# Sheet5_MCU_PowerDecoupling.net
KiCad netlist of a schematic drawn in Altium Designer
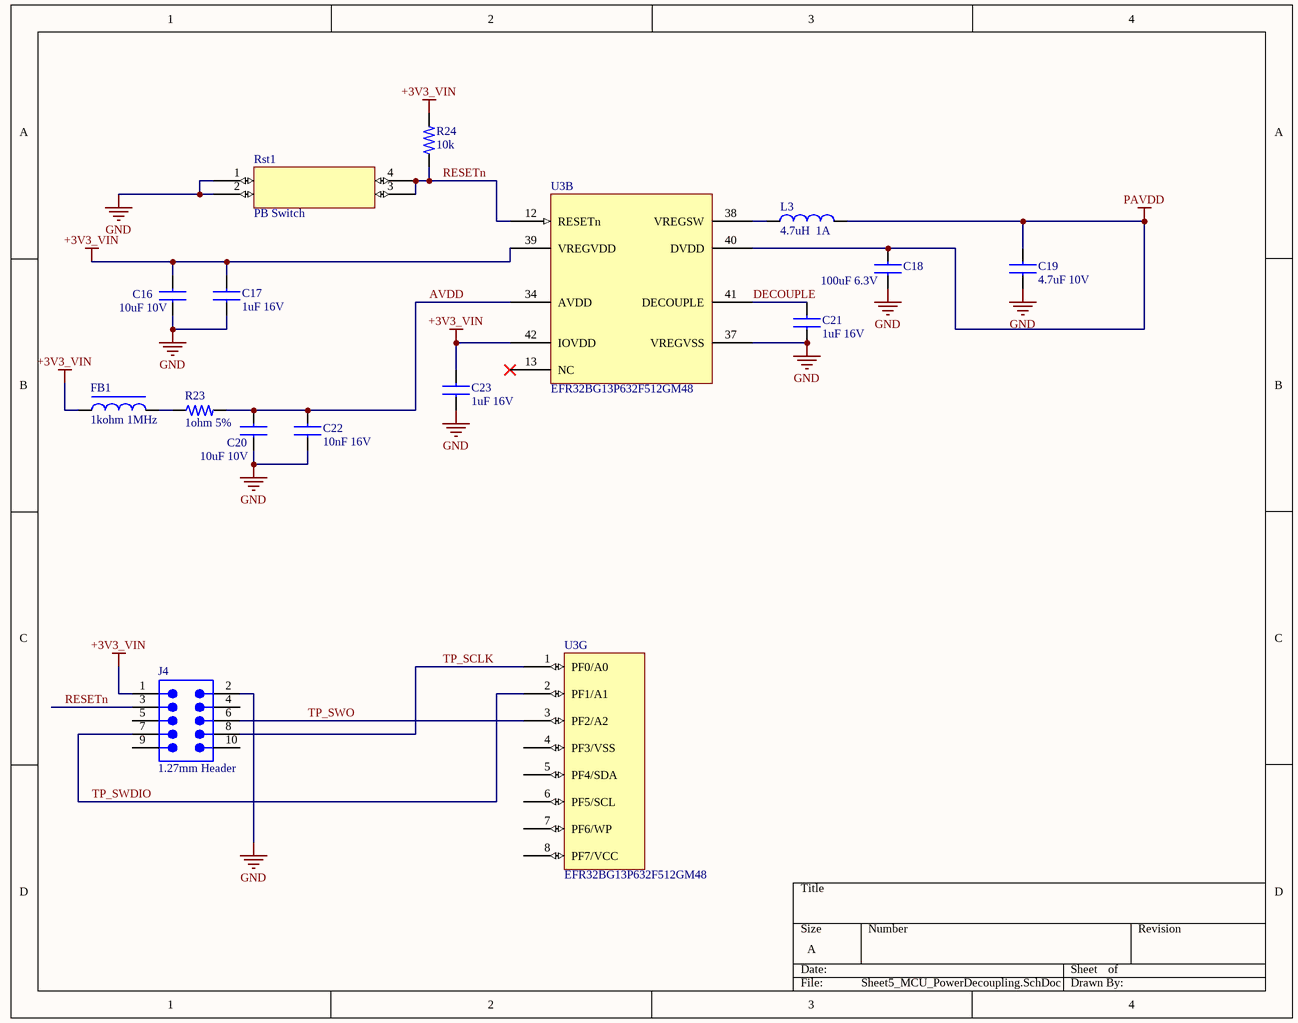
[diagram p0: Sheet5_MCU_PowerDecoupling.SchDoc]

(export (version "E")
  (design (tool "Eeschema 10.0.6"))
  (components
    (comp (ref "C16")
      (value "10uF 10V")
      (footprint "CAP_0805_1_4MM")
      (description "CAP CER 10UF 10V X5R 0805")
      (fields
        (field (name "MANUFACTURER") "KEMET")
        (field (name "MANUFACTURER PART NUMBER") "C0805C106K8PACTU")
      )
      (libsource (lib "LPEDT_Parts") (part "C0805C106K8PACTU"))
    )
    (comp (ref "C17")
      (value "1uF 16V")
      (footprint "CAP_0603_1MM")
      (fields
        (field (name "MANUFACTURER") "KEMET")
        (field (name "MANUFACTURER PART NUMBER") "C0603C105K4RAC7411")
        (field (name "TOLERANCE") "10%")
      )
      (libsource (lib "LPEDT_Parts") (part "C0603C105K4RAC7411"))
    )
    (comp (ref "C18")
      (value "100uF 6.3V")
      (footprint "RES_1206_310X16")
      (description "1206 100 uF 6.3 V ±20% Tolerance X5R SMT Multilayer Ceramic Capacitor")
      (libsource (lib "LPEDT_Parts") (part "GRM31CR60J107ME39L"))
    )
    (comp (ref "C19")
      (value "4.7uF 10V")
      (footprint "CAP_0603_1MM")
      (description "Cap Ceramic 4.7uF 10V X5R 10% SMD 0603 85°C Paper T/R")
      (fields
        (field (name "MANUFACTURER") "KEMET")
        (field (name "MANUFACTURER PART NUMBER") "C0603C475K8PAC7411")
      )
      (libsource (lib "LPEDT_Parts") (part "C0603C475K8PAC7411"))
    )
    (comp (ref "C20")
      (value "10uF 10V")
      (footprint "CAP_0805_1_4MM")
      (description "CAP CER 10UF 10V X5R 0805")
      (fields
        (field (name "MANUFACTURER") "KEMET")
        (field (name "MANUFACTURER PART NUMBER") "C0805C106K8PACTU")
      )
      (libsource (lib "LPEDT_Parts") (part "C0805C106K8PACTU"))
    )
    (comp (ref "C21")
      (value "1uF 16V")
      (footprint "CAP_0603_1MM")
      (fields
        (field (name "MANUFACTURER") "KEMET")
        (field (name "MANUFACTURER PART NUMBER") "C0603C105K4RAC7411")
        (field (name "TOLERANCE") "10%")
      )
      (libsource (lib "LPEDT_Parts") (part "C0603C105K4RAC7411"))
    )
    (comp (ref "C22")
      (value "10nF 16V")
      (footprint "CAP_0805_1_4MM")
      (description "Cap Cer 0603 10NF 16V X7R 10%")
      (fields
        (field (name "MANUFACTURER") "KEMET")
        (field (name "MANUFACTURER PART NUMBER") "C0603C103K4REC7867")
      )
      (libsource (lib "LPEDT_Parts") (part "C0603C103K4REC7867"))
    )
    (comp (ref "C23")
      (value "1uF 16V")
      (footprint "CAP_0603_1MM")
      (fields
        (field (name "MANUFACTURER") "KEMET")
        (field (name "MANUFACTURER PART NUMBER") "C0603C105K4RAC7411")
        (field (name "TOLERANCE") "10%")
      )
      (libsource (lib "LPEDT_Parts") (part "C0603C105K4RAC7411"))
    )
    (comp (ref "FB1")
      (value "1kohm 1MHz")
      (footprint "CAP_0603_1MM")
      (fields
        (field (name "MANUFACTURER") "Wurth Electronics")
        (field (name "MANUFACTURER PART NUMBER") "74279266")
        (field (name "TOLERANCE") "25%")
      )
      (libsource (lib "LPEDT_Parts") (part "74279266"))
    )
    (comp (ref "J4")
      (value "1.27mm Header")
      (footprint "SAMTEC_FTSH-105-XX-X-DV")
      (fields
        (field (name "MANUFACTURER") "Samtec")
        (field (name "MANUFACTURER PART NUMBER") "FTSH-105-01-L-DV-K-TR")
      )
      (libsource (lib "LPEDT_Parts") (part "FTSH-105-01-L-DV-K-TR"))
    )
    (comp (ref "L3")
      (value "4.7uH  1A")
      (footprint "IND_2828x30")
      (fields
        (field (name "MANUFACTURER") "Wurth Electronics")
        (field (name "MANUFACTURER PART NUMBER") "744029004")
        (field (name "TOLERANCE") "30%")
      )
      (libsource (lib "LPEDT_Parts") (part "744029004"))
    )
    (comp (ref "R23")
      (value "1ohm 5%")
      (footprint "RES_0603_1608X06")
      (description "Res Thick Film 0603 1 Ohm 5% 0.1W(1/10W) ±200ppm/C Molded SMD Paper T/R")
      (fields
        (field (name "MANUFACTURER") "Stackpole Electronics")
        (field (name "MANUFACTURER PART NUMBER") "RMCF0603JT1R00")
      )
      (libsource (lib "LPEDT_Parts") (part "RMCF0603JT1R00"))
    )
    (comp (ref "R24")
      (value "10k")
      (footprint "RES_0805_2X1_25MM")
      (description "RES 10K OHM 1% 1/8W 0805")
      (fields
        (field (name "MANUFACTURER") "Stackpole Electronics")
        (field (name "MANUFACTURER PART NUMBER") "RMCF0805FT10K0")
      )
      (libsource (lib "LPEDT_Parts") (part "RMCF0805FT10K0"))
    )
    (comp (ref "Rst1")
      (value "PB Switch")
      (footprint "DFN300P450X290-4N")
      (description "Switch Tactile N.O. SPST Round Button Gull Wing 0.05A 12VDC 100000Cycles 2.45N SMD T/R")
      (fields
        (field (name "MANUFACTURER") "ITT C&K")
        (field (name "MANUFACTURER PART NUMBER") "PTS647SK38SMTR2LFS")
      )
      (libsource (lib "LPEDT_Parts") (part "PTS647SK38SMTR2LFS"))
    )
    (comp (ref "U3")
      (value "EFR32BG13P632F512GM48")
      (footprint "QFN50P700X700X90_HS-49N")
      (description "BLUE PREMIUM QFN48 2.4G 19 DBM B")
      (fields
        (field (name "MANUFACTURER") "Silicon Labs")
        (field (name "MANUFACTURER PART NUMBER") "EFR32BG13P732F512GM48-B")
      )
      (libsource (lib "LPEDT_Parts") (part "EFR32BG13P732F512GM48-B_1"))
    )
  )
  (nets
    (net (code "1") (name "+3V3_VIN") (class "Default")
      (node (ref "C16") (pin "1") (pinfunction "1_1") (pintype "passive"))
      (node (ref "C17") (pin "1") (pinfunction "1_1") (pintype "passive"))
      (node (ref "C23") (pin "1") (pinfunction "1_1") (pintype "passive"))
      (node (ref "FB1") (pin "1") (pinfunction "1_1") (pintype "passive"))
      (node (ref "J4") (pin "1") (pinfunction "1_1") (pintype "passive"))
      (node (ref "R24") (pin "2") (pinfunction "2_2") (pintype "passive"))
      (node (ref "U3") (pin "39") (pinfunction "VREGVDD_39") (pintype "power_in"))
      (node (ref "U3") (pin "42") (pinfunction "IOVDD_42") (pintype "power_in"))
    )
    (net (code "2") (name "/AVDD") (class "Default")
      (node (ref "C20") (pin "1") (pinfunction "1_1") (pintype "passive"))
      (node (ref "C22") (pin "1") (pinfunction "1_1") (pintype "passive"))
      (node (ref "R23") (pin "2") (pinfunction "2_2") (pintype "passive"))
      (node (ref "U3") (pin "34") (pinfunction "AVDD_34") (pintype "power_in"))
    )
    (net (code "3") (name "/DECOUPLE") (class "Default")
      (node (ref "C21") (pin "1") (pinfunction "1_1") (pintype "passive"))
      (node (ref "U3") (pin "41") (pinfunction "DECOUPLE_41") (pintype "power_in"))
    )
    (net (code "4") (name "/RESETn") (class "Default")
      (node (ref "J4") (pin "3") (pinfunction "3_3") (pintype "passive"))
      (node (ref "R24") (pin "1") (pinfunction "1_1") (pintype "passive"))
      (node (ref "Rst1") (pin "3") (pinfunction "LO_A_3") (pintype "bidirectional"))
      (node (ref "Rst1") (pin "4") (pinfunction "LO_B_4") (pintype "bidirectional"))
      (node (ref "U3") (pin "12") (pinfunction "RESETn_12") (pintype "input"))
    )
    (net (code "5") (name "/TP_SCLK") (class "Default")
      (node (ref "J4") (pin "8") (pinfunction "8_8") (pintype "passive"))
      (node (ref "U3") (pin "1") (pinfunction "PF0/A0_1") (pintype "bidirectional"))
    )
    (net (code "6") (name "/TP_SWDIO") (class "Default")
      (node (ref "J4") (pin "7") (pinfunction "7_7") (pintype "passive"))
      (node (ref "U3") (pin "2") (pinfunction "PF1/A1_2") (pintype "bidirectional"))
    )
    (net (code "7") (name "/TP_SWO") (class "Default")
      (node (ref "J4") (pin "6") (pinfunction "6_6") (pintype "passive"))
      (node (ref "U3") (pin "3") (pinfunction "PF2/A2_3") (pintype "bidirectional"))
    )
    (net (code "8") (name "GND") (class "Default")
      (node (ref "C16") (pin "2") (pinfunction "2_2") (pintype "passive"))
      (node (ref "C17") (pin "2") (pinfunction "2_2") (pintype "passive"))
      (node (ref "C18") (pin "2") (pinfunction "2_2") (pintype "passive"))
      (node (ref "C19") (pin "2") (pinfunction "2_2") (pintype "passive"))
      (node (ref "C20") (pin "2") (pinfunction "2_2") (pintype "passive"))
      (node (ref "C21") (pin "2") (pinfunction "2_2") (pintype "passive"))
      (node (ref "C22") (pin "2") (pinfunction "2_2") (pintype "passive"))
      (node (ref "C23") (pin "2") (pinfunction "2_2") (pintype "passive"))
      (node (ref "J4") (pin "2") (pinfunction "2_2") (pintype "passive"))
      (node (ref "Rst1") (pin "1") (pinfunction "HI_A_1") (pintype "bidirectional"))
      (node (ref "Rst1") (pin "2") (pinfunction "HI_B_2") (pintype "bidirectional"))
      (node (ref "U3") (pin "37") (pinfunction "VREGVSS_37") (pintype "power_in"))
    )
    (net (code "9") (name "Net-(FB1-Pad2)") (class "Default")
      (node (ref "FB1") (pin "2") (pinfunction "2_2") (pintype "passive"))
      (node (ref "R23") (pin "1") (pinfunction "1_1") (pintype "passive"))
    )
    (net (code "10") (name "Net-(U3B-VREGSW)") (class "Default")
      (node (ref "L3") (pin "1") (pinfunction "1_1") (pintype "passive"))
      (node (ref "U3") (pin "38") (pinfunction "VREGSW_38") (pintype "power_in"))
    )
    (net (code "11") (name "PAVDD") (class "Default")
      (node (ref "C18") (pin "1") (pinfunction "1_1") (pintype "passive"))
      (node (ref "C19") (pin "1") (pinfunction "1_1") (pintype "passive"))
      (node (ref "L3") (pin "2") (pinfunction "2_2") (pintype "passive"))
      (node (ref "U3") (pin "40") (pinfunction "DVDD_40") (pintype "power_in"))
    )
    (net (code "12") (name "unconnected-(J4-Pad4)") (class "Default")
      (node (ref "J4") (pin "4") (pinfunction "4_4") (pintype "passive"))
    )
    (net (code "13") (name "unconnected-(J4-Pad5)") (class "Default")
      (node (ref "J4") (pin "5") (pinfunction "5_5") (pintype "passive"))
    )
    (net (code "14") (name "unconnected-(J4-Pad9)") (class "Default")
      (node (ref "J4") (pin "9") (pinfunction "9_9") (pintype "passive"))
    )
    (net (code "15") (name "unconnected-(J4-Pad10)") (class "Default")
      (node (ref "J4") (pin "10") (pinfunction "10_10") (pintype "passive"))
    )
    (net (code "16") (name "unconnected-(U3B-NC-Pad13)") (class "Default")
      (node (ref "U3") (pin "13") (pinfunction "NC_13") (pintype "passive+no_connect"))
    )
    (net (code "17") (name "unconnected-(U3G-PF3{slash}VSS-Pad4)") (class "Default")
      (node (ref "U3") (pin "4") (pinfunction "PF3/VSS_4") (pintype "bidirectional"))
    )
    (net (code "18") (name "unconnected-(U3G-PF4{slash}SDA-Pad5)") (class "Default")
      (node (ref "U3") (pin "5") (pinfunction "PF4/SDA_5") (pintype "bidirectional"))
    )
    (net (code "19") (name "unconnected-(U3G-PF5{slash}SCL-Pad6)") (class "Default")
      (node (ref "U3") (pin "6") (pinfunction "PF5/SCL_6") (pintype "bidirectional"))
    )
    (net (code "20") (name "unconnected-(U3G-PF6{slash}WP-Pad7)") (class "Default")
      (node (ref "U3") (pin "7") (pinfunction "PF6/WP_7") (pintype "bidirectional"))
    )
    (net (code "21") (name "unconnected-(U3G-PF7{slash}VCC-Pad8)") (class "Default")
      (node (ref "U3") (pin "8") (pinfunction "PF7/VCC_8") (pintype "bidirectional"))
    )
  )
)
